# flank_detection.net
KiCad netlist of a schematic drawn in EAGLE
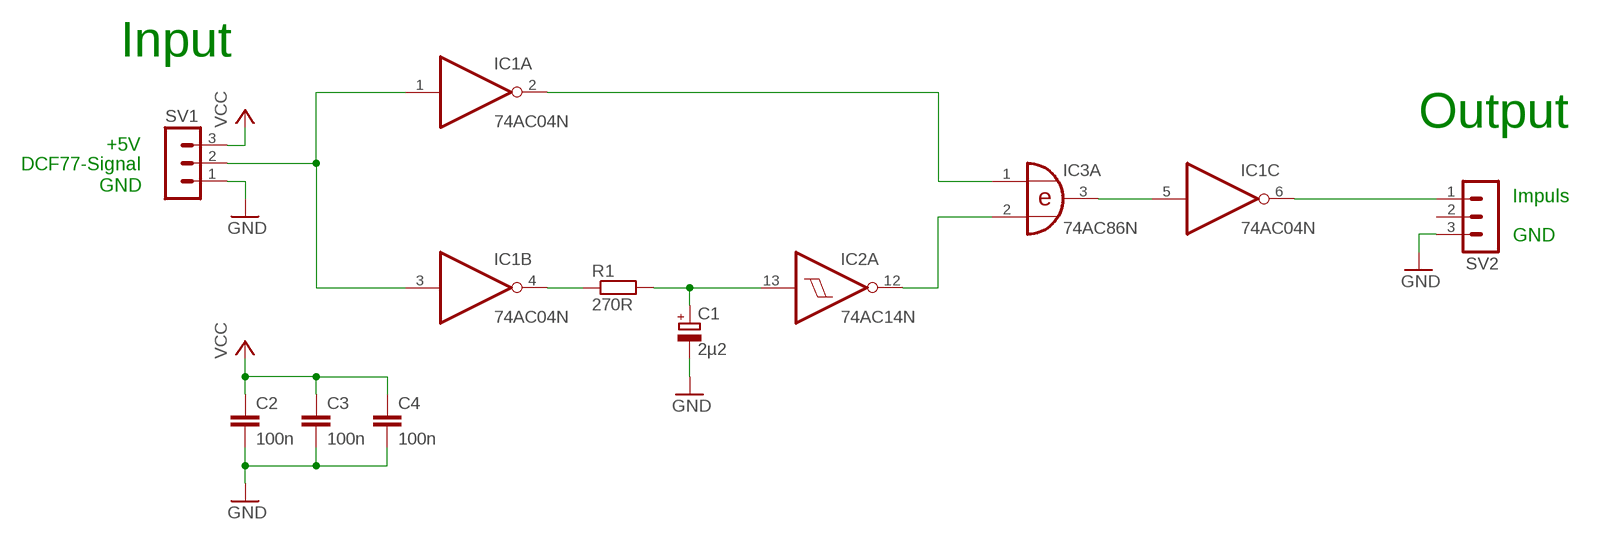
[diagram p0: schematic, sheet 1]

(export (version "E")
  (design (tool "Eeschema 10.0.6"))
  (components
    (comp (ref "C1")
      (value "2µ2")
      (footprint "eagle-import:E2,5-6E")
      (libsource (lib "eagle-import") (part "CPOL-EUE2,5-6E"))
    )
    (comp (ref "C2")
      (value "100n")
      (footprint "eagle-import:C050-024X044")
      (libsource (lib "eagle-import") (part "C-EU050-024X044"))
    )
    (comp (ref "C3")
      (value "100n")
      (footprint "eagle-import:C050-024X044")
      (libsource (lib "eagle-import") (part "C-EU050-024X044"))
    )
    (comp (ref "C4")
      (value "100n")
      (footprint "eagle-import:C050-024X044")
      (libsource (lib "eagle-import") (part "C-EU050-024X044"))
    )
    (comp (ref "IC1")
      (value "74AC04N")
      (footprint "eagle-import:DIL14")
      (libsource (lib "eagle-import") (part "7404NAC"))
    )
    (comp (ref "IC2")
      (value "74AC14N")
      (footprint "eagle-import:DIL14")
      (libsource (lib "eagle-import") (part "7414NAC"))
    )
    (comp (ref "IC3")
      (value "74AC86N")
      (footprint "eagle-import:DIL14")
      (libsource (lib "eagle-import") (part "7486NAC"))
    )
    (comp (ref "R1")
      (value "270R")
      (footprint "eagle-import:0204_5")
      (libsource (lib "eagle-import") (part "R-EU_0204/5"))
    )
    (comp (ref "SV1")
      (value "MA03-1")
      (footprint "eagle-import:MA03-1")
      (libsource (lib "eagle-import") (part "MA03-1"))
    )
    (comp (ref "SV2")
      (value "MA03-1")
      (footprint "eagle-import:MA03-1")
      (libsource (lib "eagle-import") (part "MA03-1"))
    )
  )
  (nets
    (net (code "1") (name "GND") (class "Default")
      (node (ref "C1") (pin "-") (pinfunction "-_-") (pintype "passive"))
      (node (ref "C2") (pin "2") (pinfunction "2_2") (pintype "passive"))
      (node (ref "C3") (pin "2") (pinfunction "2_2") (pintype "passive"))
      (node (ref "C4") (pin "2") (pinfunction "2_2") (pintype "passive"))
      (node (ref "SV1") (pin "1") (pinfunction "1_1") (pintype "passive"))
      (node (ref "SV2") (pin "3") (pinfunction "3_3") (pintype "passive"))
    )
    (net (code "2") (name "Net-(IC1A-I)") (class "Default")
      (node (ref "IC1") (pin "1") (pinfunction "I_1") (pintype "input"))
      (node (ref "IC1") (pin "3") (pinfunction "I_3") (pintype "input"))
      (node (ref "SV1") (pin "2") (pinfunction "2_2") (pintype "passive"))
    )
    (net (code "3") (name "Net-(IC1A-O)") (class "Default")
      (node (ref "IC1") (pin "2") (pinfunction "O_2") (pintype "output"))
      (node (ref "IC3") (pin "1") (pinfunction "I0_1") (pintype "input"))
    )
    (net (code "4") (name "Net-(IC1B-O)") (class "Default")
      (node (ref "IC1") (pin "4") (pinfunction "O_4") (pintype "output"))
      (node (ref "R1") (pin "1") (pinfunction "1_1") (pintype "passive"))
    )
    (net (code "5") (name "Net-(IC1C-I)") (class "Default")
      (node (ref "IC1") (pin "5") (pinfunction "I_5") (pintype "input"))
      (node (ref "IC3") (pin "3") (pinfunction "O_3") (pintype "output"))
    )
    (net (code "6") (name "Net-(IC1C-O)") (class "Default")
      (node (ref "IC1") (pin "6") (pinfunction "O_6") (pintype "output"))
      (node (ref "SV2") (pin "1") (pinfunction "1_1") (pintype "passive"))
    )
    (net (code "7") (name "Net-(IC2A-I)") (class "Default")
      (node (ref "C1") (pin "+") (pinfunction "+_+") (pintype "passive"))
      (node (ref "IC2") (pin "13") (pinfunction "I_13") (pintype "input"))
      (node (ref "R1") (pin "2") (pinfunction "2_2") (pintype "passive"))
    )
    (net (code "8") (name "Net-(IC2A-O)") (class "Default")
      (node (ref "IC2") (pin "12") (pinfunction "O_12") (pintype "output"))
      (node (ref "IC3") (pin "2") (pinfunction "I1_2") (pintype "input"))
    )
    (net (code "9") (name "VCC") (class "Default")
      (node (ref "C2") (pin "1") (pinfunction "1_1") (pintype "passive"))
      (node (ref "C3") (pin "1") (pinfunction "1_1") (pintype "passive"))
      (node (ref "C4") (pin "1") (pinfunction "1_1") (pintype "passive"))
      (node (ref "SV1") (pin "3") (pinfunction "3_3") (pintype "passive"))
    )
    (net (code "10") (name "unconnected-(SV2-Pad2)") (class "Default")
      (node (ref "SV2") (pin "2") (pinfunction "2_2") (pintype "passive"))
    )
  )
)
